# power_board.net
KiCad netlist of a schematic drawn in Altium Designer
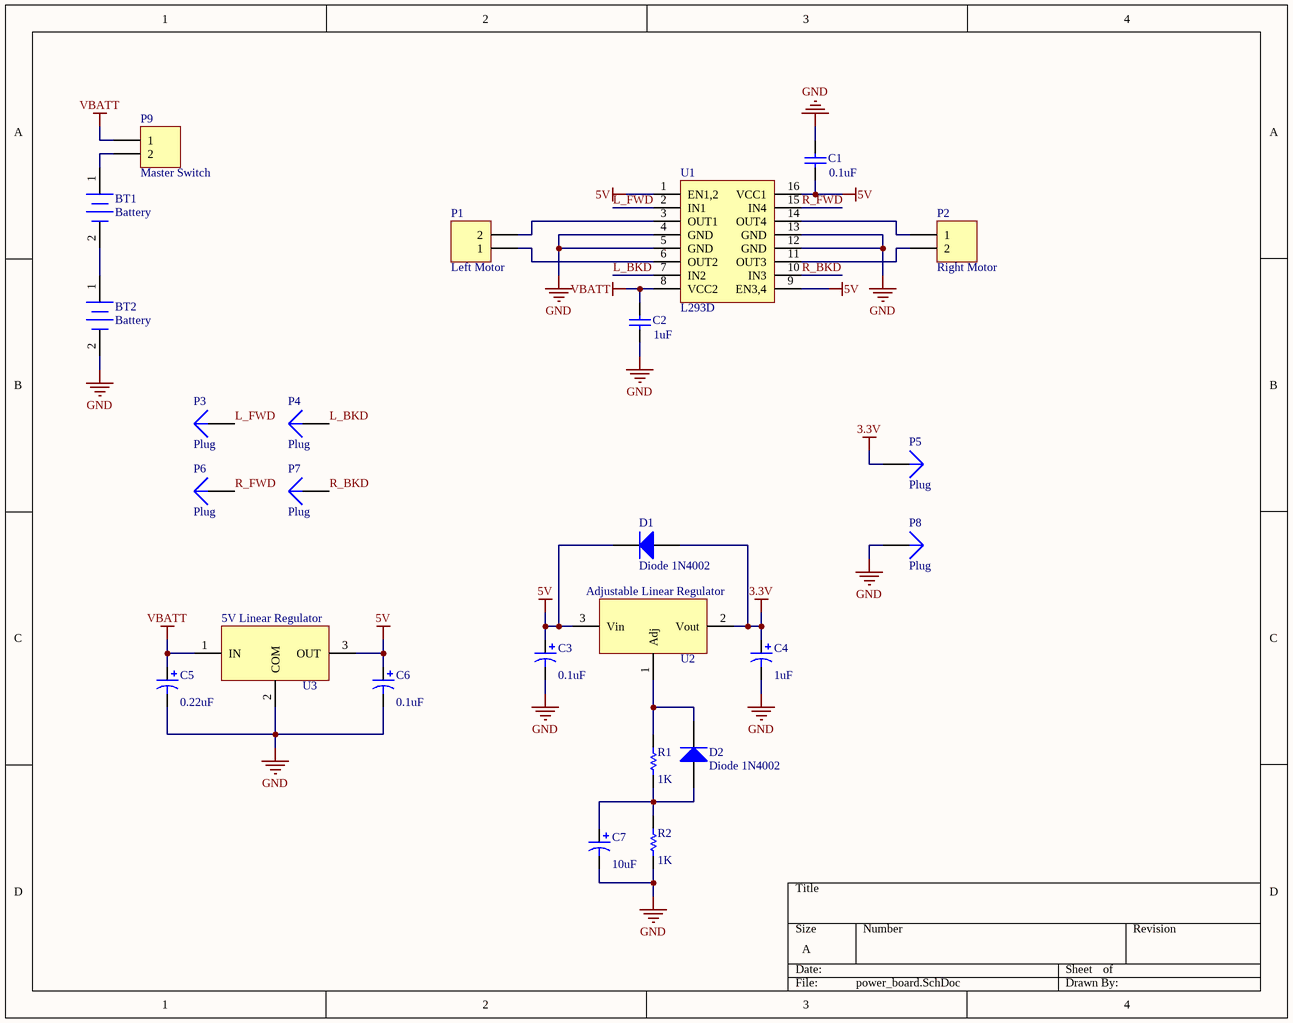
[diagram p0: power_board.SchDoc]

(export (version "E")
  (design (tool "Eeschema 10.0.6"))
  (components
    (comp (ref "BT1")
      (value "Battery")
      (footprint "VBATT")
      (description "Multicell Battery")
      (fields (field (name "PUBLISHER") "Altium Limited"))
      (libsource (lib "Miscellaneous Devices") (part "Battery"))
    )
    (comp (ref "BT2")
      (value "Battery")
      (footprint "VBATT")
      (description "Multicell Battery")
      (fields (field (name "PUBLISHER") "Altium Limited"))
      (libsource (lib "Miscellaneous Devices") (part "Battery"))
    )
    (comp (ref "C1")
      (value "0.1uF")
      (footprint "AXIAL-0.3")
      (description "Capacitor")
      (fields (field (name "Comment") "Cap") (field (name "PUBLISHER") "Altium Limited"))
      (libsource (lib "Miscellaneous Devices") (part "Cap"))
    )
    (comp (ref "C2")
      (value "1uF")
      (footprint "AXIAL-0.3")
      (description "Capacitor")
      (fields (field (name "Comment") "Cap") (field (name "PUBLISHER") "Altium Limited"))
      (libsource (lib "Miscellaneous Devices") (part "Cap"))
    )
    (comp (ref "C3")
      (value "0.1uF")
      (footprint "AXIAL-0.3")
      (description "Polarized Capacitor (Surface Mount)")
      (fields (field (name "Comment") "Cap Pol3") (field (name "PUBLISHER") "Altium Limited"))
      (libsource (lib "Miscellaneous Devices") (part "Cap Pol3"))
    )
    (comp (ref "C4")
      (value "1uF")
      (footprint "AXIAL-0.3")
      (description "Polarized Capacitor (Surface Mount)")
      (fields (field (name "Comment") "Cap Pol3") (field (name "PUBLISHER") "Altium Limited"))
      (libsource (lib "Miscellaneous Devices") (part "Cap Pol3"))
    )
    (comp (ref "C5")
      (value "0.22uF")
      (footprint "AXIAL-0.3")
      (description "Polarized Capacitor (Surface Mount)")
      (fields (field (name "Comment") "Cap Pol3") (field (name "PUBLISHER") "Altium Limited"))
      (libsource (lib "Miscellaneous Devices") (part "Cap Pol3"))
    )
    (comp (ref "C6")
      (value "0.1uF")
      (footprint "AXIAL-0.3")
      (description "Polarized Capacitor (Surface Mount)")
      (fields (field (name "Comment") "Cap Pol3") (field (name "PUBLISHER") "Altium Limited"))
      (libsource (lib "Miscellaneous Devices") (part "Cap Pol3"))
    )
    (comp (ref "C7")
      (value "10uF")
      (footprint "AXIAL-0.3")
      (description "Polarized Capacitor (Surface Mount)")
      (fields (field (name "Comment") "Cap Pol3") (field (name "PUBLISHER") "Altium Limited"))
      (libsource (lib "Miscellaneous Devices") (part "Cap Pol3"))
    )
    (comp (ref "D1")
      (value "Diode 1N4002")
      (footprint "DO-41")
      (description "1 Amp General Purpose Rectifier")
      (fields (field (name "PUBLISHER") "Altium Limited"))
      (libsource (lib "Miscellaneous Devices") (part "Diode 1N4002"))
    )
    (comp (ref "D2")
      (value "Diode 1N4002")
      (footprint "DO-41")
      (description "1 Amp General Purpose Rectifier")
      (fields (field (name "PUBLISHER") "Altium Limited"))
      (libsource (lib "Miscellaneous Devices") (part "Diode 1N4002"))
    )
    (comp (ref "P1")
      (value "Left Motor")
      (footprint "Screw Terminal")
      (description "Header, 2-Pin")
      (fields (field (name "PUBLISHER") "Altium Limited"))
      (libsource (lib "") (part "Header 2_1"))
    )
    (comp (ref "P2")
      (value "Right Motor")
      (footprint "Screw Terminal")
      (description "Header, 2-Pin")
      (fields (field (name "PUBLISHER") "Altium Limited"))
      (libsource (lib "Miscellaneous Connectors") (part "Header 2"))
    )
    (comp (ref "P3")
      (value "Plug")
      (footprint "STANDOFF")
      (fields (field (name "PUBLISHER") "Altium Limited"))
      (libsource (lib "Miscellaneous Connectors") (part "Plug"))
    )
    (comp (ref "P4")
      (value "Plug")
      (footprint "STANDOFF")
      (fields (field (name "PUBLISHER") "Altium Limited"))
      (libsource (lib "Miscellaneous Connectors") (part "Plug"))
    )
    (comp (ref "P5")
      (value "Plug")
      (footprint "STANDOFF")
      (fields (field (name "PUBLISHER") "Altium Limited"))
      (libsource (lib "Miscellaneous Connectors") (part "Plug"))
    )
    (comp (ref "P6")
      (value "Plug")
      (footprint "STANDOFF")
      (fields (field (name "PUBLISHER") "Altium Limited"))
      (libsource (lib "Miscellaneous Connectors") (part "Plug"))
    )
    (comp (ref "P7")
      (value "Plug")
      (footprint "STANDOFF")
      (fields (field (name "PUBLISHER") "Altium Limited"))
      (libsource (lib "Miscellaneous Connectors") (part "Plug"))
    )
    (comp (ref "P8")
      (value "Plug")
      (footprint "STANDOFF")
      (fields (field (name "PUBLISHER") "Altium Limited"))
      (libsource (lib "Miscellaneous Connectors") (part "Plug"))
    )
    (comp (ref "P9")
      (value "Master Switch")
      (footprint "Screw Terminal")
      (description "Header, 2-Pin")
      (fields (field (name "PUBLISHER") "Altium Limited"))
      (libsource (lib "Miscellaneous Connectors") (part "Header 2"))
    )
    (comp (ref "R1")
      (value "1K")
      (footprint "AXIAL-0.3")
      (description "Resistor")
      (fields (field (name "Comment") "Res1") (field (name "PUBLISHER") "Altium Limited"))
      (libsource (lib "Miscellaneous Devices") (part "Res1"))
    )
    (comp (ref "R2")
      (value "1K")
      (footprint "AXIAL-0.3")
      (description "Resistor")
      (fields (field (name "Comment") "Res1") (field (name "PUBLISHER") "Altium Limited"))
      (libsource (lib "Miscellaneous Devices") (part "Res1"))
    )
    (comp (ref "U1") (value "L293D") (footprint "DIP-16") (libsource (lib "power_sch_lib") (part "L293D")))
    (comp (ref "U2")
      (value "Adjustable Linear Regulator")
      (footprint "TO-220AB")
      (libsource (lib "power_sch_lib") (part "LM317T"))
    )
    (comp (ref "U3")
      (value "5V Linear Regulator")
      (footprint "TO-220AB")
      (libsource (lib "power_sch_lib") (part "LM7805C"))
    )
  )
  (nets
    (net (code "1") (name "/L_BKD") (class "Default")
      (node (ref "P4") (pin "1") (pinfunction "1_1") (pintype "passive"))
      (node (ref "U1") (pin "7") (pinfunction "IN2_7") (pintype "passive"))
    )
    (net (code "2") (name "/L_FWD") (class "Default")
      (node (ref "P3") (pin "1") (pinfunction "1_1") (pintype "passive"))
      (node (ref "U1") (pin "2") (pinfunction "IN1_2") (pintype "passive"))
    )
    (net (code "3") (name "/R_BKD") (class "Default")
      (node (ref "P7") (pin "1") (pinfunction "1_1") (pintype "passive"))
      (node (ref "U1") (pin "10") (pinfunction "IN3_10") (pintype "passive"))
    )
    (net (code "4") (name "/R_FWD") (class "Default")
      (node (ref "P6") (pin "1") (pinfunction "1_1") (pintype "passive"))
      (node (ref "U1") (pin "15") (pinfunction "IN4_15") (pintype "passive"))
    )
    (net (code "5") (name "3.3V") (class "Default")
      (node (ref "C4") (pin "1") (pinfunction "1_1") (pintype "passive"))
      (node (ref "D1") (pin "1") (pinfunction "A_1") (pintype "passive"))
      (node (ref "P5") (pin "1") (pinfunction "1_1") (pintype "passive"))
      (node (ref "U2") (pin "2") (pinfunction "Vout_2") (pintype "passive"))
    )
    (net (code "6") (name "5V") (class "Default")
      (node (ref "C1") (pin "1") (pinfunction "1_1") (pintype "passive"))
      (node (ref "C3") (pin "1") (pinfunction "1_1") (pintype "passive"))
      (node (ref "C6") (pin "1") (pinfunction "1_1") (pintype "passive"))
      (node (ref "D1") (pin "2") (pinfunction "K_2") (pintype "passive"))
      (node (ref "U1") (pin "1") (pinfunction "EN1,2_1") (pintype "passive"))
      (node (ref "U1") (pin "16") (pinfunction "VCC1_16") (pintype "passive"))
      (node (ref "U1") (pin "9") (pinfunction "EN3,4_9") (pintype "passive"))
      (node (ref "U2") (pin "3") (pinfunction "Vin_3") (pintype "passive"))
      (node (ref "U3") (pin "3") (pinfunction "OUT_3") (pintype "passive"))
    )
    (net (code "7") (name "GND") (class "Default")
      (node (ref "BT2") (pin "2") (pinfunction "-_2") (pintype "passive"))
      (node (ref "C1") (pin "2") (pinfunction "2_2") (pintype "passive"))
      (node (ref "C2") (pin "1") (pinfunction "1_1") (pintype "passive"))
      (node (ref "C3") (pin "2") (pinfunction "2_2") (pintype "passive"))
      (node (ref "C4") (pin "2") (pinfunction "2_2") (pintype "passive"))
      (node (ref "C5") (pin "2") (pinfunction "2_2") (pintype "passive"))
      (node (ref "C6") (pin "2") (pinfunction "2_2") (pintype "passive"))
      (node (ref "C7") (pin "2") (pinfunction "2_2") (pintype "passive"))
      (node (ref "P8") (pin "1") (pinfunction "1_1") (pintype "passive"))
      (node (ref "R2") (pin "1") (pinfunction "1_1") (pintype "passive"))
      (node (ref "U1") (pin "12") (pinfunction "GND_12") (pintype "passive"))
      (node (ref "U1") (pin "13") (pinfunction "GND_13") (pintype "passive"))
      (node (ref "U1") (pin "4") (pinfunction "GND_4") (pintype "passive"))
      (node (ref "U1") (pin "5") (pinfunction "GND_5") (pintype "passive"))
      (node (ref "U3") (pin "2") (pinfunction "COM_2") (pintype "passive"))
    )
    (net (code "8") (name "Net-(BT1-+)") (class "Default")
      (node (ref "BT1") (pin "1") (pinfunction "+_1") (pintype "passive"))
      (node (ref "P9") (pin "2") (pinfunction "2_2") (pintype "passive"))
    )
    (net (code "9") (name "Net-(BT1--)") (class "Default")
      (node (ref "BT1") (pin "2") (pinfunction "-_2") (pintype "passive"))
      (node (ref "BT2") (pin "1") (pinfunction "+_1") (pintype "passive"))
    )
    (net (code "10") (name "Net-(D2-A)") (class "Default")
      (node (ref "C7") (pin "1") (pinfunction "1_1") (pintype "passive"))
      (node (ref "D2") (pin "1") (pinfunction "A_1") (pintype "passive"))
      (node (ref "R1") (pin "1") (pinfunction "1_1") (pintype "passive"))
      (node (ref "R2") (pin "2") (pinfunction "2_2") (pintype "passive"))
    )
    (net (code "11") (name "Net-(D2-K)") (class "Default")
      (node (ref "D2") (pin "2") (pinfunction "K_2") (pintype "passive"))
      (node (ref "R1") (pin "2") (pinfunction "2_2") (pintype "passive"))
      (node (ref "U2") (pin "1") (pinfunction "Adj_1") (pintype "passive"))
    )
    (net (code "12") (name "Net-(U1-OUT1)") (class "Default")
      (node (ref "P1") (pin "2") (pinfunction "2_2") (pintype "passive"))
      (node (ref "U1") (pin "3") (pinfunction "OUT1_3") (pintype "passive"))
    )
    (net (code "13") (name "Net-(U1-OUT2)") (class "Default")
      (node (ref "P1") (pin "1") (pinfunction "1_1") (pintype "passive"))
      (node (ref "U1") (pin "6") (pinfunction "OUT2_6") (pintype "passive"))
    )
    (net (code "14") (name "Net-(U1-OUT3)") (class "Default")
      (node (ref "P2") (pin "2") (pinfunction "2_2") (pintype "passive"))
      (node (ref "U1") (pin "11") (pinfunction "OUT3_11") (pintype "passive"))
    )
    (net (code "15") (name "Net-(U1-OUT4)") (class "Default")
      (node (ref "P2") (pin "1") (pinfunction "1_1") (pintype "passive"))
      (node (ref "U1") (pin "14") (pinfunction "OUT4_14") (pintype "passive"))
    )
    (net (code "16") (name "VBATT") (class "Default")
      (node (ref "C2") (pin "2") (pinfunction "2_2") (pintype "passive"))
      (node (ref "C5") (pin "1") (pinfunction "1_1") (pintype "passive"))
      (node (ref "P9") (pin "1") (pinfunction "1_1") (pintype "passive"))
      (node (ref "U1") (pin "8") (pinfunction "VCC2_8") (pintype "passive"))
      (node (ref "U3") (pin "1") (pinfunction "IN_1") (pintype "passive"))
    )
  )
)
